# PWR.net
KiCad netlist of a schematic drawn in Altium Designer
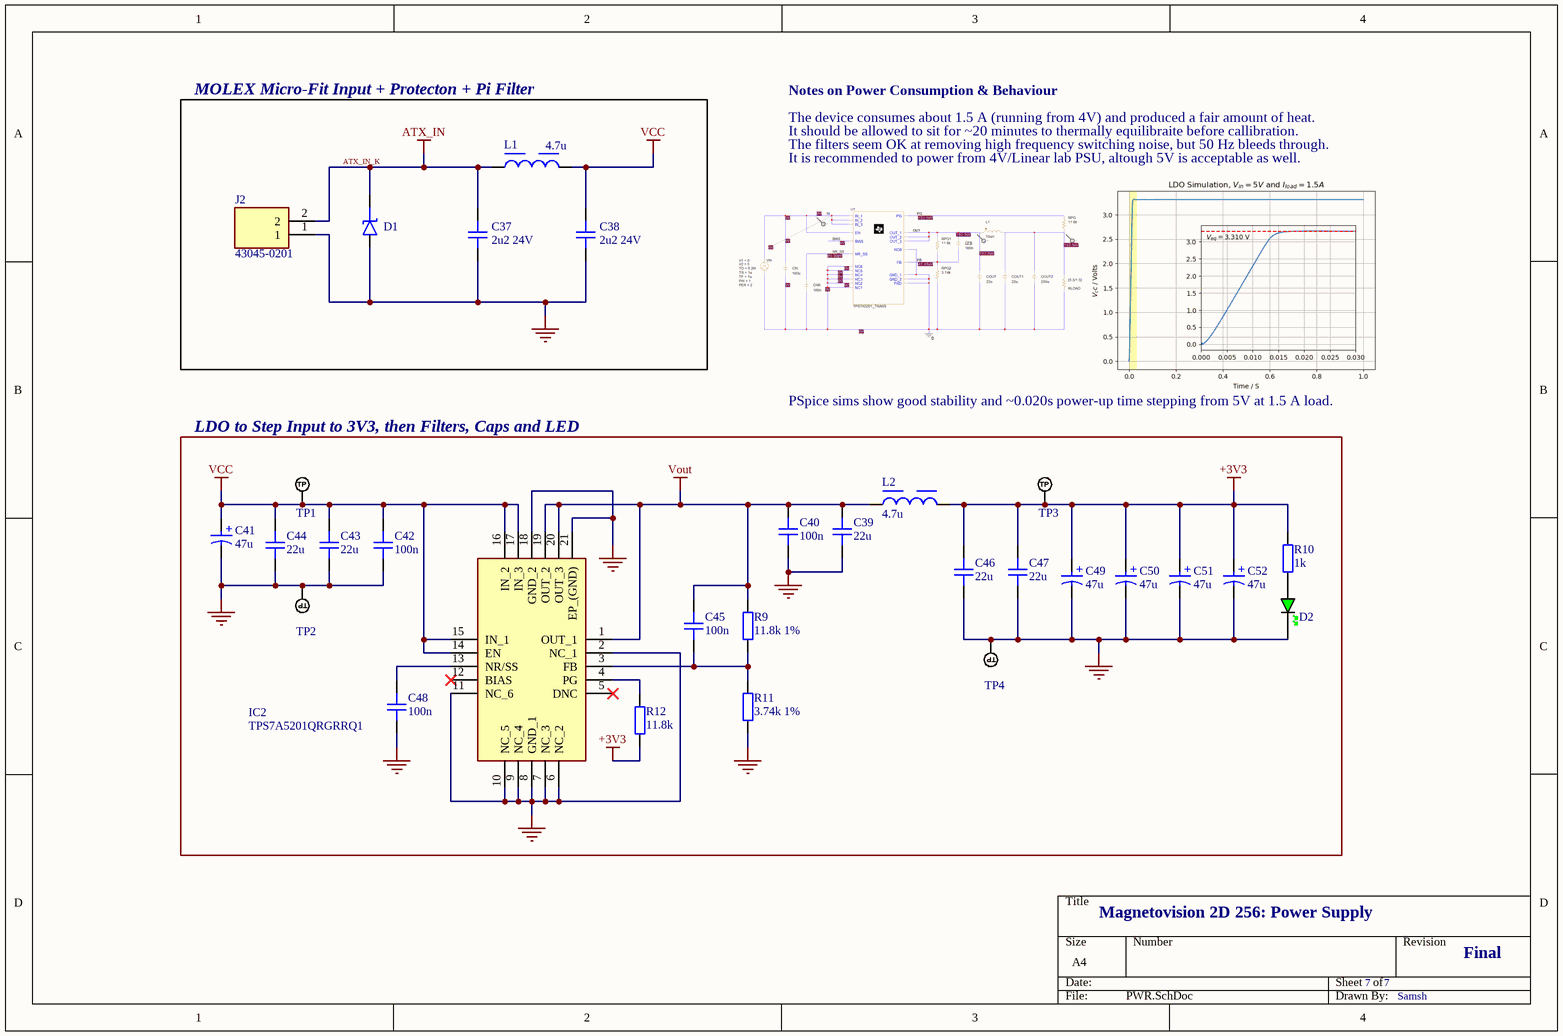
[diagram p0: PWR.SchDoc]

(export (version "E")
  (design (tool "Eeschema 10.0.6"))
  (components
    (comp (ref "C37")
      (value "2u2 24V")
      (footprint "CAP_0805")
      (description "Capacitor SMD 0805")
      (fields (field (name "SOURCE") "Schematic-Lib-PhilsLab.SchLib"))
      (libsource (lib "Samsh Nanoelectronics") (part "CAP_EL_NP_5MM"))
    )
    (comp (ref "C38")
      (value "2u2 24V")
      (footprint "CAP_0805")
      (description "Capacitor SMD 0805")
      (fields (field (name "SOURCE") "Schematic-Lib-PhilsLab.SchLib"))
      (libsource (lib "Samsh Nanoelectronics") (part "CAP_EL_NP_5MM"))
    )
    (comp (ref "C39")
      (value "22u")
      (footprint "CAP_0805")
      (description "Capacitor SMD 0805")
      (fields (field (name "SOURCE") "Schematic-Lib-PhilsLab.SchLib"))
      (libsource (lib "Samsh Nanoelectronics") (part "CAP_EL_NP_5MM"))
    )
    (comp (ref "C40")
      (value "100n")
      (footprint "CAP_0603")
      (description "Capacitor SMD 0603")
      (fields (field (name "SOURCE") "Schematic-Lib-PhilsLab.SchLib"))
      (libsource (lib "Samsh Nanoelectronics") (part "CAP_EL_NP_5MM"))
    )
    (comp (ref "C41")
      (value "47u")
      (footprint "WCAP-ASLI_D6.3H5.5")
      (description "865080543009 Alum. Electrolytic Cap 47µF 35V 6.3mmV-Chip WCAP-ASLI; Lifetime 2000h +105°C")
      (fields (field (name "TOLERANCE") "20%"))
      (libsource (lib "Altium Content Vault") (part "Capacitor_Polarized"))
    )
    (comp (ref "C42")
      (value "100n")
      (footprint "CAP_0603")
      (description "Capacitor SMD 0603")
      (fields (field (name "SOURCE") "Schematic-Lib-PhilsLab.SchLib"))
      (libsource (lib "Samsh Nanoelectronics") (part "CAP_EL_NP_5MM"))
    )
    (comp (ref "C43")
      (value "22u")
      (footprint "CAP_0805")
      (description "Capacitor SMD 0805")
      (fields (field (name "SOURCE") "Schematic-Lib-PhilsLab.SchLib"))
      (libsource (lib "Samsh Nanoelectronics") (part "CAP_EL_NP_5MM"))
    )
    (comp (ref "C44")
      (value "22u")
      (footprint "CAP_0805")
      (description "Capacitor SMD 0805")
      (fields (field (name "SOURCE") "Schematic-Lib-PhilsLab.SchLib"))
      (libsource (lib "Samsh Nanoelectronics") (part "CAP_EL_NP_5MM"))
    )
    (comp (ref "C45")
      (value "100n")
      (footprint "CAP_0603")
      (description "Capacitor SMD 0603")
      (fields (field (name "SOURCE") "Schematic-Lib-PhilsLab.SchLib"))
      (libsource (lib "Samsh Nanoelectronics") (part "CAP_EL_NP_5MM"))
    )
    (comp (ref "C46")
      (value "22u")
      (footprint "CAP_0805")
      (description "Capacitor SMD 0805")
      (fields (field (name "SOURCE") "Schematic-Lib-PhilsLab.SchLib"))
      (libsource (lib "Samsh Nanoelectronics") (part "CAP_EL_NP_5MM"))
    )
    (comp (ref "C47")
      (value "22u")
      (footprint "CAP_0805")
      (description "Capacitor SMD 0805")
      (fields (field (name "SOURCE") "Schematic-Lib-PhilsLab.SchLib"))
      (libsource (lib "Samsh Nanoelectronics") (part "CAP_EL_NP_5MM"))
    )
    (comp (ref "C48")
      (value "100n")
      (footprint "CAP_0603")
      (description "Capacitor SMD 0603")
      (fields (field (name "SOURCE") "Schematic-Lib-PhilsLab.SchLib"))
      (libsource (lib "Samsh Nanoelectronics") (part "CAP_EL_NP_5MM"))
    )
    (comp (ref "C49")
      (value "47u")
      (footprint "WCAP-ASLI_D6.3H5.5")
      (description "865080543009 Alum. Electrolytic Cap 47µF 35V 6.3mmV-Chip WCAP-ASLI; Lifetime 2000h +105°C")
      (fields (field (name "TOLERANCE") "20%"))
      (libsource (lib "Altium Content Vault") (part "Capacitor_Polarized"))
    )
    (comp (ref "C50")
      (value "47u")
      (footprint "WCAP-ASLI_D6.3H5.5")
      (description "865080543009 Alum. Electrolytic Cap 47µF 35V 6.3mmV-Chip WCAP-ASLI; Lifetime 2000h +105°C")
      (fields (field (name "TOLERANCE") "20%"))
      (libsource (lib "Altium Content Vault") (part "Capacitor_Polarized"))
    )
    (comp (ref "C51")
      (value "47u")
      (footprint "WCAP-ASLI_D6.3H5.5")
      (description "865080543009 Alum. Electrolytic Cap 47µF 35V 6.3mmV-Chip WCAP-ASLI; Lifetime 2000h +105°C")
      (fields (field (name "TOLERANCE") "20%"))
      (libsource (lib "Altium Content Vault") (part "Capacitor_Polarized"))
    )
    (comp (ref "C52")
      (value "47u")
      (footprint "WCAP-ASLI_D6.3H5.5")
      (description "865080543009 Alum. Electrolytic Cap 47µF 35V 6.3mmV-Chip WCAP-ASLI; Lifetime 2000h +105°C")
      (fields (field (name "TOLERANCE") "20%"))
      (libsource (lib "Altium Content Vault") (part "Capacitor_Polarized"))
    )
    (comp (ref "D1")
      (value "SMA Shottky")
      (footprint "DO-214AC-2 (SMA)")
      (description "Diode Schottky SMD SMA (DO-214AA)")
      (fields (field (name "SOURCE") "Schematic-Lib-PhilsLab.SchLib"))
      (libsource (lib "Samsh Nanoelectronics") (part "D_SCHOTTKY_SOD_323"))
    )
    (comp (ref "D2")
      (value "LED_0603_GREEN")
      (footprint "LED_0603_GREEN")
      (description "LED 0603 GREEN SMD")
      (fields (field (name "SOURCE") "Schematic-Lib-PhilsLab.SchLib"))
      (libsource (lib "Samsh Nanoelectronics") (part "LED_0805_GREEN"))
    )
    (comp (ref "IC2")
      (value "TPS7A5201QRGRRQ1")
      (footprint "SamacSys:QFN50P350X350X100-21N-D")
      (description "Integrated Circuit")
      (fields (field (name "MOUSER PART NUMBER") "595-TPS7A5201QRGRRQ1"))
      (libsource (lib "*") (part "TPS7A5201QRGRRQ1"))
    )
    (comp (ref "J2")
      (value "43045-0201")
      (footprint "SamacSys:43045-02YY")
      (description "Connector")
      (fields (field (name "MOUSER PART NUMBER") "538-43045-0201"))
      (libsource (lib "*") (part "43045-0201"))
    )
    (comp (ref "L1")
      (value "4.7u")
      (footprint "WE-LHMI_7030")
      (fields (field (name "TOLERANCE") "20%"))
      (libsource (lib "Altium Content Vault") (part "Inductor - 3"))
    )
    (comp (ref "L2")
      (value "4.7u")
      (footprint "WE-LHMI_7030")
      (fields (field (name "TOLERANCE") "20%"))
      (libsource (lib "") (part "Inductor - 3_1"))
    )
    (comp (ref "R9")
      (value "11.8k 1%")
      (footprint "RES_0603")
      (description "Resistor SMD 0603")
      (fields (field (name "SOURCE") "Schematic-Lib-PhilsLab.SchLib"))
      (libsource (lib "Samsh Nanoelectronics") (part "RES_5931"))
    )
    (comp (ref "R10")
      (value "1k")
      (footprint "RES_0603")
      (description "Resistor SMD 0603")
      (fields (field (name "SOURCE") "Schematic-Lib-PhilsLab.SchLib"))
      (libsource (lib "Samsh Nanoelectronics") (part "RES_5931"))
    )
    (comp (ref "R11")
      (value "3.74k 1%")
      (footprint "RES_0603")
      (description "Resistor SMD 0603")
      (fields (field (name "SOURCE") "Schematic-Lib-PhilsLab.SchLib"))
      (libsource (lib "Samsh Nanoelectronics") (part "RES_5931"))
    )
    (comp (ref "R12")
      (value "11.8k")
      (footprint "RES_0603")
      (description "Resistor SMD 0603")
      (fields (field (name "SOURCE") "Schematic-Lib-PhilsLab.SchLib"))
      (libsource (lib "Samsh Nanoelectronics") (part "RES_5931"))
    )
    (comp (ref "TP1")
      (value "TEST_POINT_RND_1MM")
      (footprint "PAD_RND_1MM")
      (description "Test Point Round 1mm (NO BOM)")
      (fields (field (name "SOURCE") "Schematic-Lib-PhilsLab.SchLib"))
      (libsource (lib "Samsh Nanoelectronics") (part "TEST_POINT_RND_1MM"))
    )
    (comp (ref "TP2")
      (value "TEST_POINT_RND_1MM")
      (footprint "PAD_RND_1MM")
      (description "Test Point Round 1mm (NO BOM)")
      (fields (field (name "SOURCE") "Schematic-Lib-PhilsLab.SchLib"))
      (libsource (lib "Samsh Nanoelectronics") (part "TEST_POINT_RND_1MM"))
    )
    (comp (ref "TP3")
      (value "TEST_POINT_RND_1MM")
      (footprint "PAD_RND_1MM")
      (description "Test Point Round 1mm (NO BOM)")
      (fields (field (name "SOURCE") "Schematic-Lib-PhilsLab.SchLib"))
      (libsource (lib "Samsh Nanoelectronics") (part "TEST_POINT_RND_1MM"))
    )
    (comp (ref "TP4")
      (value "TEST_POINT_RND_1MM")
      (footprint "PAD_RND_1MM")
      (description "Test Point Round 1mm (NO BOM)")
      (fields (field (name "SOURCE") "Schematic-Lib-PhilsLab.SchLib"))
      (libsource (lib "Samsh Nanoelectronics") (part "TEST_POINT_RND_1MM"))
    )
  )
  (nets
    (net (code "1") (name "+3V3") (class "Default")
      (node (ref "C46") (pin "2") (pinfunction "2_2") (pintype "passive"))
      (node (ref "C47") (pin "2") (pinfunction "2_2") (pintype "passive"))
      (node (ref "C49") (pin "1") (pinfunction "P_1") (pintype "passive"))
      (node (ref "C50") (pin "1") (pinfunction "P_1") (pintype "passive"))
      (node (ref "C51") (pin "1") (pinfunction "P_1") (pintype "passive"))
      (node (ref "C52") (pin "1") (pinfunction "P_1") (pintype "passive"))
      (node (ref "L2") (pin "1") (pinfunction "1_1") (pintype "passive"))
      (node (ref "R10") (pin "2") (pinfunction "2_2") (pintype "passive"))
      (node (ref "R12") (pin "1") (pinfunction "1_1") (pintype "passive"))
      (node (ref "TP3") (pin "1") (pinfunction "TP_1") (pintype "passive"))
    )
    (net (code "2") (name "ATX_IN") (class "Default")
      (node (ref "C37") (pin "2") (pinfunction "2_2") (pintype "passive"))
      (node (ref "D1") (pin "K") (pinfunction "K_K") (pintype "passive"))
      (node (ref "J2") (pin "2") (pinfunction "2_2") (pintype "passive"))
      (node (ref "L1") (pin "1") (pinfunction "1_1") (pintype "passive"))
    )
    (net (code "3") (name "GND") (class "Default")
      (node (ref "C37") (pin "1") (pinfunction "1_1") (pintype "passive"))
      (node (ref "C38") (pin "1") (pinfunction "1_1") (pintype "passive"))
      (node (ref "C39") (pin "1") (pinfunction "1_1") (pintype "passive"))
      (node (ref "C40") (pin "1") (pinfunction "1_1") (pintype "passive"))
      (node (ref "C41") (pin "2") (pinfunction "N_2") (pintype "passive"))
      (node (ref "C42") (pin "1") (pinfunction "1_1") (pintype "passive"))
      (node (ref "C43") (pin "1") (pinfunction "1_1") (pintype "passive"))
      (node (ref "C44") (pin "1") (pinfunction "1_1") (pintype "passive"))
      (node (ref "C46") (pin "1") (pinfunction "1_1") (pintype "passive"))
      (node (ref "C47") (pin "1") (pinfunction "1_1") (pintype "passive"))
      (node (ref "C48") (pin "1") (pinfunction "1_1") (pintype "passive"))
      (node (ref "C49") (pin "2") (pinfunction "N_2") (pintype "passive"))
      (node (ref "C50") (pin "2") (pinfunction "N_2") (pintype "passive"))
      (node (ref "C51") (pin "2") (pinfunction "N_2") (pintype "passive"))
      (node (ref "C52") (pin "2") (pinfunction "N_2") (pintype "passive"))
      (node (ref "D1") (pin "A") (pinfunction "A_A") (pintype "passive"))
      (node (ref "D2") (pin "K") (pinfunction "K_K") (pintype "passive"))
      (node (ref "IC2") (pin "10") (pinfunction "NC_5_10") (pintype "passive"))
      (node (ref "IC2") (pin "11") (pinfunction "NC_6_11") (pintype "passive"))
      (node (ref "IC2") (pin "18") (pinfunction "GND_2_18") (pintype "passive"))
      (node (ref "IC2") (pin "2") (pinfunction "NC_1_2") (pintype "passive"))
      (node (ref "IC2") (pin "21") (pinfunction "EP_(GND)_21") (pintype "passive"))
      (node (ref "IC2") (pin "6") (pinfunction "NC_2_6") (pintype "passive"))
      (node (ref "IC2") (pin "7") (pinfunction "NC_3_7") (pintype "passive"))
      (node (ref "IC2") (pin "8") (pinfunction "GND_1_8") (pintype "passive"))
      (node (ref "IC2") (pin "9") (pinfunction "NC_4_9") (pintype "passive"))
      (node (ref "J2") (pin "1") (pinfunction "1_1") (pintype "passive"))
      (node (ref "R11") (pin "1") (pinfunction "1_1") (pintype "passive"))
      (node (ref "TP2") (pin "1") (pinfunction "TP_1") (pintype "passive"))
      (node (ref "TP4") (pin "1") (pinfunction "TP_1") (pintype "passive"))
    )
    (net (code "4") (name "Net-(D2-PadA)") (class "Default")
      (node (ref "D2") (pin "A") (pinfunction "A_A") (pintype "passive"))
      (node (ref "R10") (pin "1") (pinfunction "1_1") (pintype "passive"))
    )
    (net (code "5") (name "Net-(IC2-FB)") (class "Default")
      (node (ref "C45") (pin "1") (pinfunction "1_1") (pintype "passive"))
      (node (ref "IC2") (pin "3") (pinfunction "FB_3") (pintype "passive"))
      (node (ref "R11") (pin "2") (pinfunction "2_2") (pintype "passive"))
      (node (ref "R9") (pin "1") (pinfunction "1_1") (pintype "passive"))
    )
    (net (code "6") (name "Net-(IC2-NR{slash}SS)") (class "Default")
      (node (ref "C48") (pin "2") (pinfunction "2_2") (pintype "passive"))
      (node (ref "IC2") (pin "13") (pinfunction "NR/SS_13") (pintype "passive"))
    )
    (net (code "7") (name "Net-(IC2-PG)") (class "Default")
      (node (ref "IC2") (pin "4") (pinfunction "PG_4") (pintype "passive"))
      (node (ref "R12") (pin "2") (pinfunction "2_2") (pintype "passive"))
    )
    (net (code "8") (name "VCC") (class "Default")
      (node (ref "C38") (pin "2") (pinfunction "2_2") (pintype "passive"))
      (node (ref "C41") (pin "1") (pinfunction "P_1") (pintype "passive"))
      (node (ref "C42") (pin "2") (pinfunction "2_2") (pintype "passive"))
      (node (ref "C43") (pin "2") (pinfunction "2_2") (pintype "passive"))
      (node (ref "C44") (pin "2") (pinfunction "2_2") (pintype "passive"))
      (node (ref "IC2") (pin "14") (pinfunction "EN_14") (pintype "passive"))
      (node (ref "IC2") (pin "15") (pinfunction "IN_1_15") (pintype "passive"))
      (node (ref "IC2") (pin "16") (pinfunction "IN_2_16") (pintype "passive"))
      (node (ref "IC2") (pin "17") (pinfunction "IN_3_17") (pintype "passive"))
      (node (ref "L1") (pin "2") (pinfunction "2_2") (pintype "passive"))
      (node (ref "TP1") (pin "1") (pinfunction "TP_1") (pintype "passive"))
    )
    (net (code "9") (name "Vout") (class "Default")
      (node (ref "C39") (pin "2") (pinfunction "2_2") (pintype "passive"))
      (node (ref "C40") (pin "2") (pinfunction "2_2") (pintype "passive"))
      (node (ref "C45") (pin "2") (pinfunction "2_2") (pintype "passive"))
      (node (ref "IC2") (pin "1") (pinfunction "OUT_1_1") (pintype "passive"))
      (node (ref "IC2") (pin "19") (pinfunction "OUT_2_19") (pintype "passive"))
      (node (ref "IC2") (pin "20") (pinfunction "OUT_3_20") (pintype "passive"))
      (node (ref "L2") (pin "2") (pinfunction "2_2") (pintype "passive"))
      (node (ref "R9") (pin "2") (pinfunction "2_2") (pintype "passive"))
    )
    (net (code "10") (name "unconnected-(IC2-BIAS-Pad12)") (class "Default")
      (node (ref "IC2") (pin "12") (pinfunction "BIAS_12") (pintype "passive+no_connect"))
    )
    (net (code "11") (name "unconnected-(IC2-DNC-Pad5)") (class "Default")
      (node (ref "IC2") (pin "5") (pinfunction "DNC_5") (pintype "passive+no_connect"))
    )
  )
)
